# LCD_16x2_with_8051.net
KiCad netlist of a schematic drawn in EAGLE
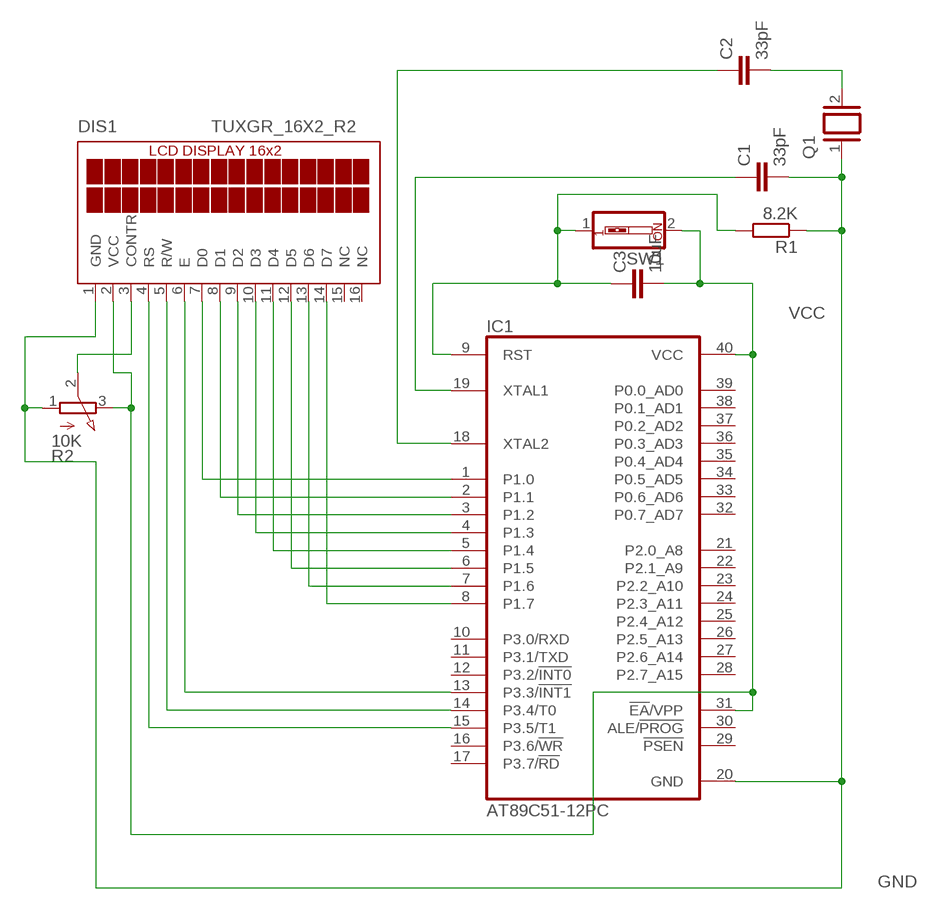
[diagram p0: schematic, sheet 1]

(export (version "E")
  (design (tool "Eeschema 10.0.6"))
  (components
    (comp (ref "C1")
      (value "33pF")
      (footprint "eagle-import:C025-025X050")
      (libsource (lib "eagle-import") (part "C-EU025-025X050"))
    )
    (comp (ref "C2")
      (value "33pF")
      (footprint "eagle-import:C025-025X050")
      (libsource (lib "eagle-import") (part "C-EU025-025X050"))
    )
    (comp (ref "C3")
      (value "10uF")
      (footprint "eagle-import:C025-025X050")
      (libsource (lib "eagle-import") (part "C-EU025-025X050"))
    )
    (comp (ref "DIS1")
      (value "TUXGR_16X2_R2")
      (footprint "eagle-import:TUXGR_16X2_R2")
      (libsource (lib "eagle-import") (part "TUXGR_16X2_R2"))
    )
    (comp (ref "IC1")
      (value "AT89C51-12PC")
      (footprint "eagle-import:DIL40")
      (libsource (lib "eagle-import") (part "AT89C51-PC12"))
    )
    (comp (ref "Q1")
      (value "XTAL")
      (footprint "eagle-import:Q")
      (libsource (lib "eagle-import") (part "XTAL"))
    )
    (comp (ref "R1")
      (value "8.2K")
      (footprint "eagle-import:0204_7")
      (libsource (lib "eagle-import") (part "R-EU_0204/7"))
    )
    (comp (ref "R2")
      (value "10K")
      (footprint "eagle-import:3RP_1610N")
      (libsource (lib "eagle-import") (part "3RP/1610N"))
    )
    (comp (ref "SW1")
      (value "SW_DIP-1")
      (footprint "eagle-import:EDG-01")
      (libsource (lib "eagle-import") (part "SW_DIP-1"))
    )
  )
  (nets
    (net (code "1") (name "/GND") (class "Default")
      (node (ref "C1") (pin "2") (pinfunction "2_2") (pintype "passive"))
      (node (ref "DIS1") (pin "1") (pinfunction "GND_1") (pintype "power_in"))
      (node (ref "IC1") (pin "20") (pinfunction "GND_20") (pintype "power_in"))
      (node (ref "Q1") (pin "1") (pinfunction "1_1") (pintype "passive"))
      (node (ref "R1") (pin "1") (pinfunction "1_1") (pintype "passive"))
      (node (ref "R2") (pin "1") (pinfunction "A_1") (pintype "passive"))
    )
    (net (code "2") (name "/VCC") (class "Default")
      (node (ref "C3") (pin "2") (pinfunction "2_2") (pintype "passive"))
      (node (ref "DIS1") (pin "2") (pinfunction "VCC_2") (pintype "power_in"))
      (node (ref "IC1") (pin "31") (pinfunction "~{EA}/VPP_31") (pintype "input"))
      (node (ref "IC1") (pin "40") (pinfunction "VCC_40") (pintype "power_in"))
      (node (ref "R2") (pin "3") (pinfunction "E_3") (pintype "passive"))
      (node (ref "SW1") (pin "2") (pinfunction "2_2") (pintype "passive"))
    )
    (net (code "3") (name "Net-(C2-Pad2)") (class "Default")
      (node (ref "C2") (pin "2") (pinfunction "2_2") (pintype "passive"))
      (node (ref "Q1") (pin "2") (pinfunction "2_2") (pintype "passive"))
    )
    (net (code "4") (name "Net-(DIS1-CONTR)") (class "Default")
      (node (ref "DIS1") (pin "3") (pinfunction "CONTR_3") (pintype "input"))
      (node (ref "R2") (pin "2") (pinfunction "S_2") (pintype "passive"))
    )
    (net (code "5") (name "Net-(DIS1-D0)") (class "Default")
      (node (ref "DIS1") (pin "7") (pinfunction "D0_7") (pintype "input"))
      (node (ref "IC1") (pin "1") (pinfunction "P1.0_1") (pintype "bidirectional"))
    )
    (net (code "6") (name "Net-(DIS1-D1)") (class "Default")
      (node (ref "DIS1") (pin "8") (pinfunction "D1_8") (pintype "input"))
      (node (ref "IC1") (pin "2") (pinfunction "P1.1_2") (pintype "bidirectional"))
    )
    (net (code "7") (name "Net-(DIS1-D2)") (class "Default")
      (node (ref "DIS1") (pin "9") (pinfunction "D2_9") (pintype "input"))
      (node (ref "IC1") (pin "3") (pinfunction "P1.2_3") (pintype "bidirectional"))
    )
    (net (code "8") (name "Net-(DIS1-D3)") (class "Default")
      (node (ref "DIS1") (pin "10") (pinfunction "D3_10") (pintype "input"))
      (node (ref "IC1") (pin "4") (pinfunction "P1.3_4") (pintype "bidirectional"))
    )
    (net (code "9") (name "Net-(DIS1-D4)") (class "Default")
      (node (ref "DIS1") (pin "11") (pinfunction "D4_11") (pintype "input"))
      (node (ref "IC1") (pin "5") (pinfunction "P1.4_5") (pintype "bidirectional"))
    )
    (net (code "10") (name "Net-(DIS1-D5)") (class "Default")
      (node (ref "DIS1") (pin "12") (pinfunction "D5_12") (pintype "input"))
      (node (ref "IC1") (pin "6") (pinfunction "P1.5_6") (pintype "bidirectional"))
    )
    (net (code "11") (name "Net-(DIS1-D6)") (class "Default")
      (node (ref "DIS1") (pin "13") (pinfunction "D6_13") (pintype "input"))
      (node (ref "IC1") (pin "7") (pinfunction "P1.6_7") (pintype "bidirectional"))
    )
    (net (code "12") (name "Net-(DIS1-D7)") (class "Default")
      (node (ref "DIS1") (pin "14") (pinfunction "D7_14") (pintype "input"))
      (node (ref "IC1") (pin "8") (pinfunction "P1.7_8") (pintype "bidirectional"))
    )
    (net (code "13") (name "Net-(DIS1-E)") (class "Default")
      (node (ref "DIS1") (pin "6") (pinfunction "E_6") (pintype "input"))
      (node (ref "IC1") (pin "13") (pinfunction "P3.3/~{INT1}_13") (pintype "bidirectional"))
    )
    (net (code "14") (name "Net-(DIS1-RS)") (class "Default")
      (node (ref "DIS1") (pin "4") (pinfunction "RS_4") (pintype "input"))
      (node (ref "IC1") (pin "15") (pinfunction "P3.5/T1_15") (pintype "bidirectional"))
    )
    (net (code "15") (name "Net-(DIS1-R{slash}W)") (class "Default")
      (node (ref "DIS1") (pin "5") (pinfunction "R/W_5") (pintype "input"))
      (node (ref "IC1") (pin "14") (pinfunction "P3.4/T0_14") (pintype "bidirectional"))
    )
    (net (code "16") (name "Net-(IC1-RST)") (class "Default")
      (node (ref "C3") (pin "1") (pinfunction "1_1") (pintype "passive"))
      (node (ref "IC1") (pin "9") (pinfunction "RST_9") (pintype "input"))
      (node (ref "R1") (pin "2") (pinfunction "2_2") (pintype "passive"))
      (node (ref "SW1") (pin "1") (pinfunction "1_1") (pintype "passive"))
    )
    (net (code "17") (name "Net-(IC1-XTAL1)") (class "Default")
      (node (ref "C1") (pin "1") (pinfunction "1_1") (pintype "passive"))
      (node (ref "IC1") (pin "19") (pinfunction "XTAL1_19") (pintype "input"))
    )
    (net (code "18") (name "Net-(IC1-XTAL2)") (class "Default")
      (node (ref "C2") (pin "1") (pinfunction "1_1") (pintype "passive"))
      (node (ref "IC1") (pin "18") (pinfunction "XTAL2_18") (pintype "input"))
    )
    (net (code "19") (name "unconnected-(DIS1-NC-Pad15)") (class "Default")
      (node (ref "DIS1") (pin "15") (pinfunction "NC_15") (pintype "no_connect"))
    )
    (net (code "20") (name "unconnected-(DIS1-NC-Pad16)") (class "Default")
      (node (ref "DIS1") (pin "16") (pinfunction "NC_16") (pintype "no_connect"))
    )
    (net (code "21") (name "unconnected-(IC1-ALE{slash}~{PROG}-Pad30)") (class "Default")
      (node (ref "IC1") (pin "30") (pinfunction "ALE/~{PROG}_30") (pintype "output"))
    )
    (net (code "22") (name "unconnected-(IC1-P0.0_AD0-Pad39)") (class "Default")
      (node (ref "IC1") (pin "39") (pinfunction "P0.0_AD0_39") (pintype "bidirectional"))
    )
    (net (code "23") (name "unconnected-(IC1-P0.1_AD1-Pad38)") (class "Default")
      (node (ref "IC1") (pin "38") (pinfunction "P0.1_AD1_38") (pintype "bidirectional"))
    )
    (net (code "24") (name "unconnected-(IC1-P0.2_AD2-Pad37)") (class "Default")
      (node (ref "IC1") (pin "37") (pinfunction "P0.2_AD2_37") (pintype "bidirectional"))
    )
    (net (code "25") (name "unconnected-(IC1-P0.3_AD3-Pad36)") (class "Default")
      (node (ref "IC1") (pin "36") (pinfunction "P0.3_AD3_36") (pintype "bidirectional"))
    )
    (net (code "26") (name "unconnected-(IC1-P0.4_AD4-Pad35)") (class "Default")
      (node (ref "IC1") (pin "35") (pinfunction "P0.4_AD4_35") (pintype "bidirectional"))
    )
    (net (code "27") (name "unconnected-(IC1-P0.5_AD5-Pad34)") (class "Default")
      (node (ref "IC1") (pin "34") (pinfunction "P0.5_AD5_34") (pintype "bidirectional"))
    )
    (net (code "28") (name "unconnected-(IC1-P0.6_AD6-Pad33)") (class "Default")
      (node (ref "IC1") (pin "33") (pinfunction "P0.6_AD6_33") (pintype "bidirectional"))
    )
    (net (code "29") (name "unconnected-(IC1-P0.7_AD7-Pad32)") (class "Default")
      (node (ref "IC1") (pin "32") (pinfunction "P0.7_AD7_32") (pintype "bidirectional"))
    )
    (net (code "30") (name "unconnected-(IC1-P2.0_A8-Pad21)") (class "Default")
      (node (ref "IC1") (pin "21") (pinfunction "P2.0_A8_21") (pintype "bidirectional"))
    )
    (net (code "31") (name "unconnected-(IC1-P2.1_A9-Pad22)") (class "Default")
      (node (ref "IC1") (pin "22") (pinfunction "P2.1_A9_22") (pintype "bidirectional"))
    )
    (net (code "32") (name "unconnected-(IC1-P2.2_A10-Pad23)") (class "Default")
      (node (ref "IC1") (pin "23") (pinfunction "P2.2_A10_23") (pintype "bidirectional"))
    )
    (net (code "33") (name "unconnected-(IC1-P2.3_A11-Pad24)") (class "Default")
      (node (ref "IC1") (pin "24") (pinfunction "P2.3_A11_24") (pintype "bidirectional"))
    )
    (net (code "34") (name "unconnected-(IC1-P2.4_A12-Pad25)") (class "Default")
      (node (ref "IC1") (pin "25") (pinfunction "P2.4_A12_25") (pintype "bidirectional"))
    )
    (net (code "35") (name "unconnected-(IC1-P2.5_A13-Pad26)") (class "Default")
      (node (ref "IC1") (pin "26") (pinfunction "P2.5_A13_26") (pintype "bidirectional"))
    )
    (net (code "36") (name "unconnected-(IC1-P2.6_A14-Pad27)") (class "Default")
      (node (ref "IC1") (pin "27") (pinfunction "P2.6_A14_27") (pintype "bidirectional"))
    )
    (net (code "37") (name "unconnected-(IC1-P2.7_A15-Pad28)") (class "Default")
      (node (ref "IC1") (pin "28") (pinfunction "P2.7_A15_28") (pintype "bidirectional"))
    )
    (net (code "38") (name "unconnected-(IC1-P3.0{slash}RXD-Pad10)") (class "Default")
      (node (ref "IC1") (pin "10") (pinfunction "P3.0/RXD_10") (pintype "bidirectional"))
    )
    (net (code "39") (name "unconnected-(IC1-P3.1{slash}TXD-Pad11)") (class "Default")
      (node (ref "IC1") (pin "11") (pinfunction "P3.1/TXD_11") (pintype "bidirectional"))
    )
    (net (code "40") (name "unconnected-(IC1-P3.2{slash}~{INT0}-Pad12)") (class "Default")
      (node (ref "IC1") (pin "12") (pinfunction "P3.2/~{INT0}_12") (pintype "bidirectional"))
    )
    (net (code "41") (name "unconnected-(IC1-P3.6{slash}~{WR}-Pad16)") (class "Default")
      (node (ref "IC1") (pin "16") (pinfunction "P3.6/~{WR}_16") (pintype "bidirectional"))
    )
    (net (code "42") (name "unconnected-(IC1-P3.7{slash}~{RD}-Pad17)") (class "Default")
      (node (ref "IC1") (pin "17") (pinfunction "P3.7/~{RD}_17") (pintype "bidirectional"))
    )
    (net (code "43") (name "unconnected-(IC1-~{PSEN}-Pad29)") (class "Default")
      (node (ref "IC1") (pin "29") (pinfunction "~{PSEN}_29") (pintype "output"))
    )
  )
)
